# Esquematico_ODJ-Raptor.net
KiCad netlist of a schematic drawn in EAGLE
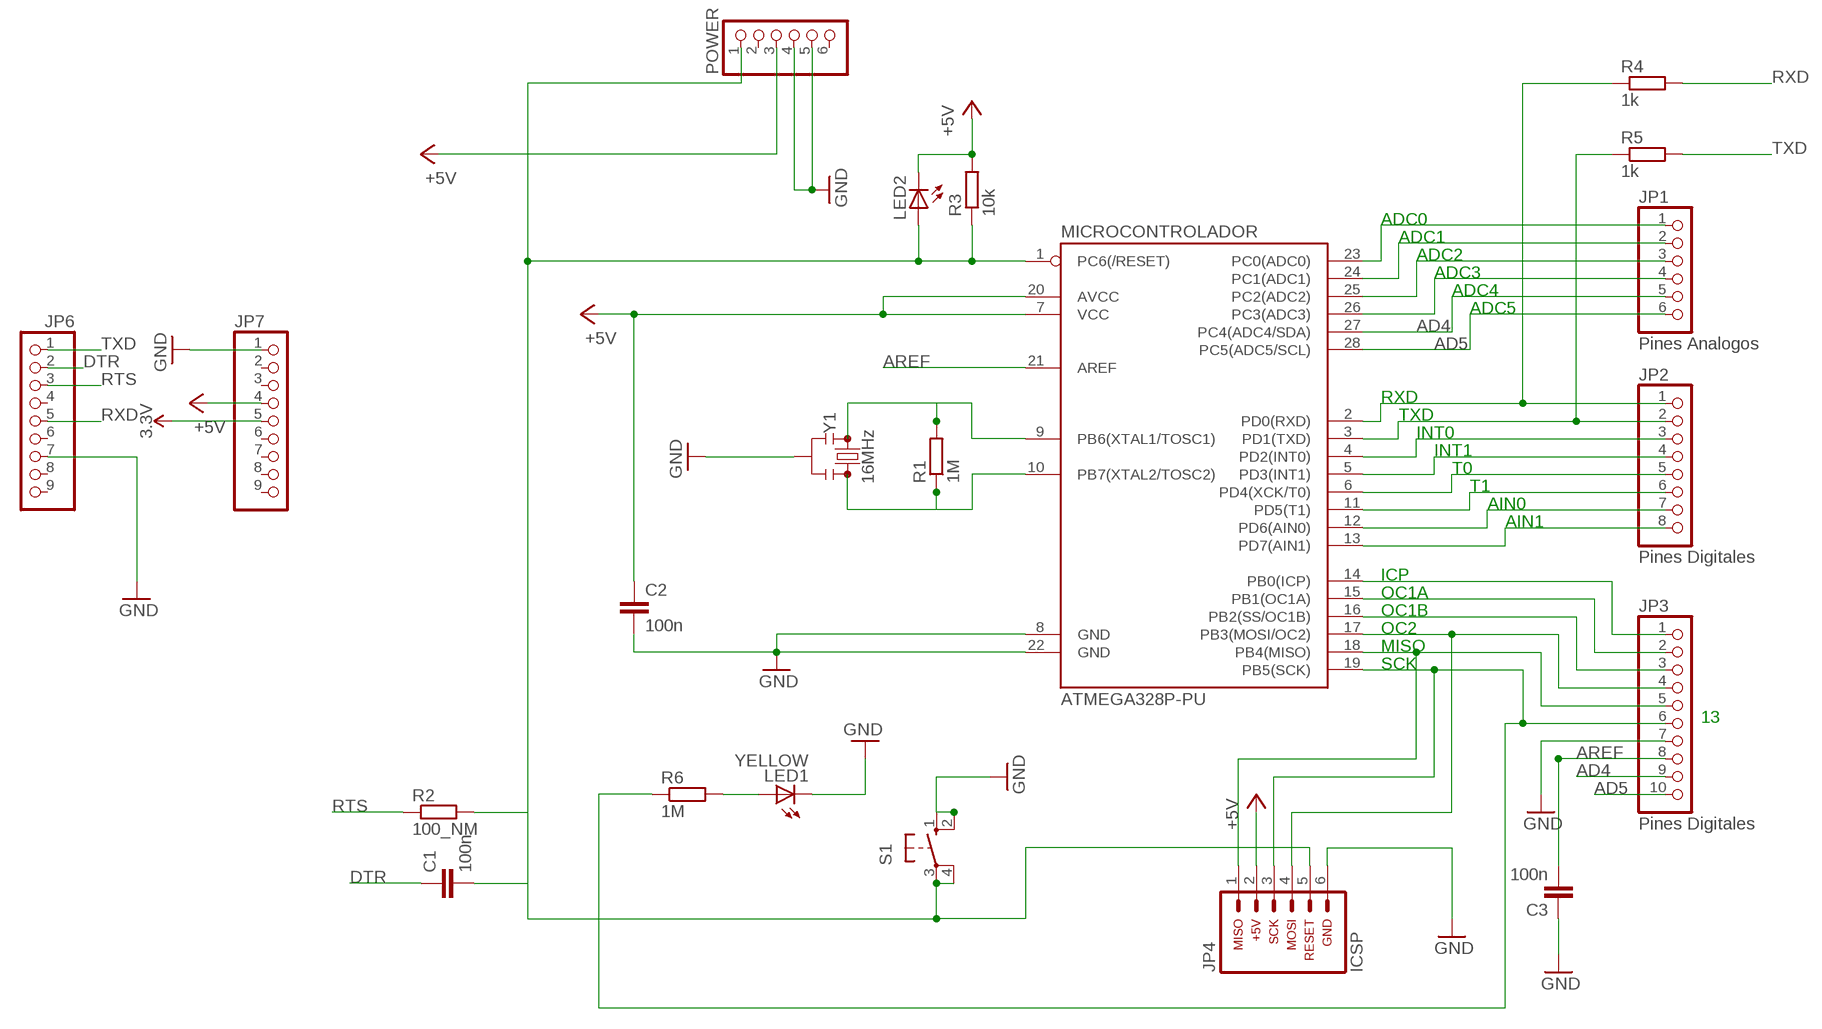
[diagram p0: schematic, sheet 1]

(export (version "E")
  (design (tool "Eeschema 10.0.6"))
  (components
    (comp (ref "C1")
      (value "100n")
      (footprint "eagle-import:C2.5-2")
      (libsource (lib "eagle-import") (part "C2.5/2"))
    )
    (comp (ref "C2")
      (value "100n")
      (footprint "eagle-import:C2.5-2")
      (libsource (lib "eagle-import") (part "C2.5/2"))
    )
    (comp (ref "C3")
      (value "100n")
      (footprint "eagle-import:C2.5-2")
      (libsource (lib "eagle-import") (part "C2.5/2"))
    )
    (comp (ref "JP1")
      (value "Pines Analogos")
      (footprint "eagle-import:1X06")
      (libsource (lib "eagle-import") (part "pinhead_PINHD-1X6"))
    )
    (comp (ref "JP2")
      (value "Pines Digitales")
      (footprint "eagle-import:1X08")
      (libsource (lib "eagle-import") (part "PINHD-1X8"))
    )
    (comp (ref "JP3")
      (value "Pines Digitales")
      (footprint "eagle-import:1X10")
      (libsource (lib "eagle-import") (part "PINHD-1X10"))
    )
    (comp (ref "JP4")
      (value "ARDUINO_CONN-ICSP")
      (footprint "eagle-import:CONN-2X03")
      (libsource (lib "eagle-import") (part "ARDUINO_CONN-ICSP"))
    )
    (comp (ref "JP6")
      (value "PINHD-1X9")
      (footprint "eagle-import:1X09-BIG")
      (libsource (lib "eagle-import") (part "PINHD-1X9"))
    )
    (comp (ref "JP7")
      (value "PINHD-1X9")
      (footprint "eagle-import:1X09-BIG")
      (libsource (lib "eagle-import") (part "PINHD-1X9"))
    )
    (comp (ref "LED1")
      (value "YELLOW")
      (footprint "eagle-import:SMARTLED-TTW")
      (libsource (lib "eagle-import") (part "LED"))
    )
    (comp (ref "LED2")
      (value "LED")
      (footprint "eagle-import:SMARTLED-TTW")
      (libsource (lib "eagle-import") (part "led_LED"))
    )
    (comp (ref "MICROCONTROLADOR")
      (value "ATMEGA328P-PU")
      (footprint "eagle-import:DIP28")
      (libsource (lib "eagle-import") (part "ATMEGA328P_PDIP"))
    )
    (comp (ref "POWER")
      (value "PINHD-1X6")
      (footprint "eagle-import:1X06")
      (libsource (lib "eagle-import") (part "PINHD-1X6"))
    )
    (comp (ref "R1")
      (value "1M")
      (footprint "eagle-import:0204_7")
      (libsource (lib "eagle-import") (part "R-EU_0204/7"))
    )
    (comp (ref "R2")
      (value "100_NM")
      (footprint "eagle-import:0204_7")
      (libsource (lib "eagle-import") (part "R-EU_0204/7"))
    )
    (comp (ref "R3")
      (value "10k")
      (footprint "eagle-import:0204_7")
      (libsource (lib "eagle-import") (part "R-EU_0204/7"))
    )
    (comp (ref "R4")
      (value "1k")
      (footprint "eagle-import:0204_7")
      (libsource (lib "eagle-import") (part "R-EU_0204/7"))
    )
    (comp (ref "R5")
      (value "1k")
      (footprint "eagle-import:0204_7")
      (libsource (lib "eagle-import") (part "R-EU_0204/7"))
    )
    (comp (ref "R6")
      (value "1M")
      (footprint "eagle-import:0204_7")
      (libsource (lib "eagle-import") (part "R-EU_0204/7"))
    )
    (comp (ref "S1")
      (value "10-XX")
      (footprint "eagle-import:B3F-10XX")
      (fields (field (name "MPN") "B3F-1000"))
      (libsource (lib "eagle-import") (part "10-XX"))
    )
    (comp (ref "Y1")
      (value "16MHz")
      (footprint "eagle-import:RESONATOR-SMD-3.2X1.3")
      (libsource (lib "eagle-import") (part "RESONATOR-16MHZSMD_3.2X1.3"))
    )
  )
  (nets
    (net (code "1") (name "+5V") (class "Default")
      (node (ref "C2") (pin "1") (pinfunction "1_1") (pintype "passive"))
      (node (ref "JP4") (pin "2") (pinfunction "2_2") (pintype "passive"))
      (node (ref "JP7") (pin "4") (pinfunction "4_4") (pintype "passive"))
      (node (ref "LED2") (pin "C@1") (pinfunction "C_C@1") (pintype "passive"))
      (node (ref "MICROCONTROLADOR") (pin "20") (pinfunction "AVCC_20") (pintype "bidirectional"))
      (node (ref "MICROCONTROLADOR") (pin "7") (pinfunction "VCC_7") (pintype "bidirectional"))
      (node (ref "POWER") (pin "3") (pinfunction "3_3") (pintype "passive"))
      (node (ref "R3") (pin "2") (pinfunction "2_2") (pintype "passive"))
    )
    (net (code "2") (name "/AD4") (class "Default")
      (node (ref "JP1") (pin "5") (pinfunction "5_5") (pintype "passive"))
      (node (ref "JP3") (pin "9") (pinfunction "9_9") (pintype "passive"))
      (node (ref "MICROCONTROLADOR") (pin "27") (pinfunction "PC4(ADC4/SDA)_27") (pintype "bidirectional"))
    )
    (net (code "3") (name "/AD5") (class "Default")
      (node (ref "JP1") (pin "6") (pinfunction "6_6") (pintype "passive"))
      (node (ref "JP3") (pin "10") (pinfunction "10_10") (pintype "passive"))
      (node (ref "MICROCONTROLADOR") (pin "28") (pinfunction "PC5(ADC5/SCL)_28") (pintype "bidirectional"))
    )
    (net (code "4") (name "/AREF") (class "Default")
      (node (ref "C3") (pin "2") (pinfunction "2_2") (pintype "passive"))
      (node (ref "JP3") (pin "8") (pinfunction "8_8") (pintype "passive"))
      (node (ref "MICROCONTROLADOR") (pin "21") (pinfunction "AREF_21") (pintype "bidirectional"))
    )
    (net (code "5") (name "/DTR") (class "Default")
      (node (ref "C1") (pin "1") (pinfunction "1_1") (pintype "passive"))
      (node (ref "JP6") (pin "2") (pinfunction "2_2") (pintype "passive"))
    )
    (net (code "6") (name "/RTS") (class "Default")
      (node (ref "JP6") (pin "3") (pinfunction "3_3") (pintype "passive"))
      (node (ref "R2") (pin "1") (pinfunction "1_1") (pintype "passive"))
    )
    (net (code "7") (name "/RXD") (class "Default")
      (node (ref "JP6") (pin "5") (pinfunction "5_5") (pintype "passive"))
      (node (ref "R4") (pin "2") (pinfunction "2_2") (pintype "passive"))
    )
    (net (code "8") (name "/TXD") (class "Default")
      (node (ref "JP6") (pin "1") (pinfunction "1_1") (pintype "passive"))
      (node (ref "R5") (pin "2") (pinfunction "2_2") (pintype "passive"))
    )
    (net (code "9") (name "3.3V") (class "Default")
      (node (ref "JP7") (pin "5") (pinfunction "5_5") (pintype "passive"))
    )
    (net (code "10") (name "GND") (class "Default")
      (node (ref "C2") (pin "2") (pinfunction "2_2") (pintype "passive"))
      (node (ref "C3") (pin "1") (pinfunction "1_1") (pintype "passive"))
      (node (ref "JP3") (pin "7") (pinfunction "7_7") (pintype "passive"))
      (node (ref "JP4") (pin "6") (pinfunction "6_6") (pintype "passive"))
      (node (ref "JP6") (pin "7") (pinfunction "7_7") (pintype "passive"))
      (node (ref "JP7") (pin "1") (pinfunction "1_1") (pintype "passive"))
      (node (ref "LED1") (pin "C@1") (pinfunction "C_C@1") (pintype "passive"))
      (node (ref "MICROCONTROLADOR") (pin "22") (pinfunction "GND_22") (pintype "bidirectional"))
      (node (ref "MICROCONTROLADOR") (pin "8") (pinfunction "GND_8") (pintype "bidirectional"))
      (node (ref "POWER") (pin "4") (pinfunction "4_4") (pintype "passive"))
      (node (ref "POWER") (pin "5") (pinfunction "5_5") (pintype "passive"))
      (node (ref "S1") (pin "1") (pinfunction "S_1") (pintype "passive"))
      (node (ref "S1") (pin "2") (pinfunction "S1_2") (pintype "passive"))
      (node (ref "Y1") (pin "2") (pinfunction "2_2") (pintype "passive"))
    )
    (net (code "11") (name "Net-(LED1-A)") (class "Default")
      (node (ref "LED1") (pin "A@1") (pinfunction "A_A@1") (pintype "passive"))
      (node (ref "R6") (pin "2") (pinfunction "2_2") (pintype "passive"))
    )
    (net (code "12") (name "Net-(LED2-A)") (class "Default")
      (node (ref "C1") (pin "2") (pinfunction "2_2") (pintype "passive"))
      (node (ref "JP4") (pin "5") (pinfunction "5_5") (pintype "passive"))
      (node (ref "LED2") (pin "A@1") (pinfunction "A_A@1") (pintype "passive"))
      (node (ref "MICROCONTROLADOR") (pin "1") (pinfunction "PC6(/RESET)_1") (pintype "bidirectional"))
      (node (ref "POWER") (pin "1") (pinfunction "1_1") (pintype "passive"))
      (node (ref "R2") (pin "2") (pinfunction "2_2") (pintype "passive"))
      (node (ref "R3") (pin "1") (pinfunction "1_1") (pintype "passive"))
      (node (ref "S1") (pin "3") (pinfunction "P_3") (pintype "passive"))
      (node (ref "S1") (pin "4") (pinfunction "P1_4") (pintype "passive"))
    )
    (net (code "13") (name "Net-(MICROCONTROLADOR-PB0(ICP))") (class "Default")
      (node (ref "JP3") (pin "1") (pinfunction "1_1") (pintype "passive"))
      (node (ref "MICROCONTROLADOR") (pin "14") (pinfunction "PB0(ICP)_14") (pintype "bidirectional"))
    )
    (net (code "14") (name "Net-(MICROCONTROLADOR-PB1(OC1A))") (class "Default")
      (node (ref "JP3") (pin "2") (pinfunction "2_2") (pintype "passive"))
      (node (ref "MICROCONTROLADOR") (pin "15") (pinfunction "PB1(OC1A)_15") (pintype "bidirectional"))
    )
    (net (code "15") (name "Net-(MICROCONTROLADOR-PB2(SS{slash}OC1B))") (class "Default")
      (node (ref "JP3") (pin "3") (pinfunction "3_3") (pintype "passive"))
      (node (ref "MICROCONTROLADOR") (pin "16") (pinfunction "PB2(SS/OC1B)_16") (pintype "bidirectional"))
    )
    (net (code "16") (name "Net-(MICROCONTROLADOR-PB3(MOSI{slash}OC2))") (class "Default")
      (node (ref "JP3") (pin "4") (pinfunction "4_4") (pintype "passive"))
      (node (ref "JP4") (pin "4") (pinfunction "4_4") (pintype "passive"))
      (node (ref "MICROCONTROLADOR") (pin "17") (pinfunction "PB3(MOSI/OC2)_17") (pintype "bidirectional"))
    )
    (net (code "17") (name "Net-(MICROCONTROLADOR-PB4(MISO))") (class "Default")
      (node (ref "JP3") (pin "5") (pinfunction "5_5") (pintype "passive"))
      (node (ref "JP4") (pin "1") (pinfunction "1_1") (pintype "passive"))
      (node (ref "MICROCONTROLADOR") (pin "18") (pinfunction "PB4(MISO)_18") (pintype "bidirectional"))
    )
    (net (code "18") (name "Net-(MICROCONTROLADOR-PB5(SCK))") (class "Default")
      (node (ref "JP3") (pin "6") (pinfunction "6_6") (pintype "passive"))
      (node (ref "JP4") (pin "3") (pinfunction "3_3") (pintype "passive"))
      (node (ref "MICROCONTROLADOR") (pin "19") (pinfunction "PB5(SCK)_19") (pintype "bidirectional"))
      (node (ref "R6") (pin "1") (pinfunction "1_1") (pintype "passive"))
    )
    (net (code "19") (name "Net-(MICROCONTROLADOR-PB6(XTAL1{slash}TOSC1))") (class "Default")
      (node (ref "MICROCONTROLADOR") (pin "9") (pinfunction "PB6(XTAL1/TOSC1)_9") (pintype "bidirectional"))
      (node (ref "R1") (pin "2") (pinfunction "2_2") (pintype "passive"))
      (node (ref "Y1") (pin "1") (pinfunction "1_1") (pintype "passive"))
    )
    (net (code "20") (name "Net-(MICROCONTROLADOR-PB7(XTAL2{slash}TOSC2))") (class "Default")
      (node (ref "MICROCONTROLADOR") (pin "10") (pinfunction "PB7(XTAL2/TOSC2)_10") (pintype "bidirectional"))
      (node (ref "R1") (pin "1") (pinfunction "1_1") (pintype "passive"))
      (node (ref "Y1") (pin "3") (pinfunction "3_3") (pintype "passive"))
    )
    (net (code "21") (name "Net-(MICROCONTROLADOR-PC0(ADC0))") (class "Default")
      (node (ref "JP1") (pin "1") (pinfunction "1_1") (pintype "passive"))
      (node (ref "MICROCONTROLADOR") (pin "23") (pinfunction "PC0(ADC0)_23") (pintype "bidirectional"))
    )
    (net (code "22") (name "Net-(MICROCONTROLADOR-PC1(ADC1))") (class "Default")
      (node (ref "JP1") (pin "2") (pinfunction "2_2") (pintype "passive"))
      (node (ref "MICROCONTROLADOR") (pin "24") (pinfunction "PC1(ADC1)_24") (pintype "bidirectional"))
    )
    (net (code "23") (name "Net-(MICROCONTROLADOR-PC2(ADC2))") (class "Default")
      (node (ref "JP1") (pin "3") (pinfunction "3_3") (pintype "passive"))
      (node (ref "MICROCONTROLADOR") (pin "25") (pinfunction "PC2(ADC2)_25") (pintype "bidirectional"))
    )
    (net (code "24") (name "Net-(MICROCONTROLADOR-PC3(ADC3))") (class "Default")
      (node (ref "JP1") (pin "4") (pinfunction "4_4") (pintype "passive"))
      (node (ref "MICROCONTROLADOR") (pin "26") (pinfunction "PC3(ADC3)_26") (pintype "bidirectional"))
    )
    (net (code "25") (name "Net-(MICROCONTROLADOR-PD0(RXD))") (class "Default")
      (node (ref "JP2") (pin "1") (pinfunction "1_1") (pintype "passive"))
      (node (ref "MICROCONTROLADOR") (pin "2") (pinfunction "PD0(RXD)_2") (pintype "bidirectional"))
      (node (ref "R4") (pin "1") (pinfunction "1_1") (pintype "passive"))
    )
    (net (code "26") (name "Net-(MICROCONTROLADOR-PD1(TXD))") (class "Default")
      (node (ref "JP2") (pin "2") (pinfunction "2_2") (pintype "passive"))
      (node (ref "MICROCONTROLADOR") (pin "3") (pinfunction "PD1(TXD)_3") (pintype "bidirectional"))
      (node (ref "R5") (pin "1") (pinfunction "1_1") (pintype "passive"))
    )
    (net (code "27") (name "Net-(MICROCONTROLADOR-PD2(INT0))") (class "Default")
      (node (ref "JP2") (pin "3") (pinfunction "3_3") (pintype "passive"))
      (node (ref "MICROCONTROLADOR") (pin "4") (pinfunction "PD2(INT0)_4") (pintype "bidirectional"))
    )
    (net (code "28") (name "Net-(MICROCONTROLADOR-PD3(INT1))") (class "Default")
      (node (ref "JP2") (pin "4") (pinfunction "4_4") (pintype "passive"))
      (node (ref "MICROCONTROLADOR") (pin "5") (pinfunction "PD3(INT1)_5") (pintype "bidirectional"))
    )
    (net (code "29") (name "Net-(MICROCONTROLADOR-PD4(XCK{slash}T0))") (class "Default")
      (node (ref "JP2") (pin "5") (pinfunction "5_5") (pintype "passive"))
      (node (ref "MICROCONTROLADOR") (pin "6") (pinfunction "PD4(XCK/T0)_6") (pintype "bidirectional"))
    )
    (net (code "30") (name "Net-(MICROCONTROLADOR-PD5(T1))") (class "Default")
      (node (ref "JP2") (pin "6") (pinfunction "6_6") (pintype "passive"))
      (node (ref "MICROCONTROLADOR") (pin "11") (pinfunction "PD5(T1)_11") (pintype "bidirectional"))
    )
    (net (code "31") (name "Net-(MICROCONTROLADOR-PD6(AIN0))") (class "Default")
      (node (ref "JP2") (pin "7") (pinfunction "7_7") (pintype "passive"))
      (node (ref "MICROCONTROLADOR") (pin "12") (pinfunction "PD6(AIN0)_12") (pintype "bidirectional"))
    )
    (net (code "32") (name "Net-(MICROCONTROLADOR-PD7(AIN1))") (class "Default")
      (node (ref "JP2") (pin "8") (pinfunction "8_8") (pintype "passive"))
      (node (ref "MICROCONTROLADOR") (pin "13") (pinfunction "PD7(AIN1)_13") (pintype "bidirectional"))
    )
    (net (code "33") (name "unconnected-(JP6-Pad4)") (class "Default")
      (node (ref "JP6") (pin "4") (pinfunction "4_4") (pintype "passive"))
    )
    (net (code "34") (name "unconnected-(JP6-Pad6)") (class "Default")
      (node (ref "JP6") (pin "6") (pinfunction "6_6") (pintype "passive"))
    )
    (net (code "35") (name "unconnected-(JP6-Pad8)") (class "Default")
      (node (ref "JP6") (pin "8") (pinfunction "8_8") (pintype "passive"))
    )
    (net (code "36") (name "unconnected-(JP6-Pad9)") (class "Default")
      (node (ref "JP6") (pin "9") (pinfunction "9_9") (pintype "passive"))
    )
    (net (code "37") (name "unconnected-(JP7-Pad2)") (class "Default")
      (node (ref "JP7") (pin "2") (pinfunction "2_2") (pintype "passive"))
    )
    (net (code "38") (name "unconnected-(JP7-Pad3)") (class "Default")
      (node (ref "JP7") (pin "3") (pinfunction "3_3") (pintype "passive"))
    )
    (net (code "39") (name "unconnected-(JP7-Pad6)") (class "Default")
      (node (ref "JP7") (pin "6") (pinfunction "6_6") (pintype "passive"))
    )
    (net (code "40") (name "unconnected-(JP7-Pad7)") (class "Default")
      (node (ref "JP7") (pin "7") (pinfunction "7_7") (pintype "passive"))
    )
    (net (code "41") (name "unconnected-(JP7-Pad8)") (class "Default")
      (node (ref "JP7") (pin "8") (pinfunction "8_8") (pintype "passive"))
    )
    (net (code "42") (name "unconnected-(JP7-Pad9)") (class "Default")
      (node (ref "JP7") (pin "9") (pinfunction "9_9") (pintype "passive"))
    )
    (net (code "43") (name "unconnected-(POWER-Pad2)") (class "Default")
      (node (ref "POWER") (pin "2") (pinfunction "2_2") (pintype "passive"))
    )
    (net (code "44") (name "unconnected-(POWER-Pad6)") (class "Default")
      (node (ref "POWER") (pin "6") (pinfunction "6_6") (pintype "passive"))
    )
  )
)
